# PCB.net
KiCad netlist of a schematic drawn in EAGLE
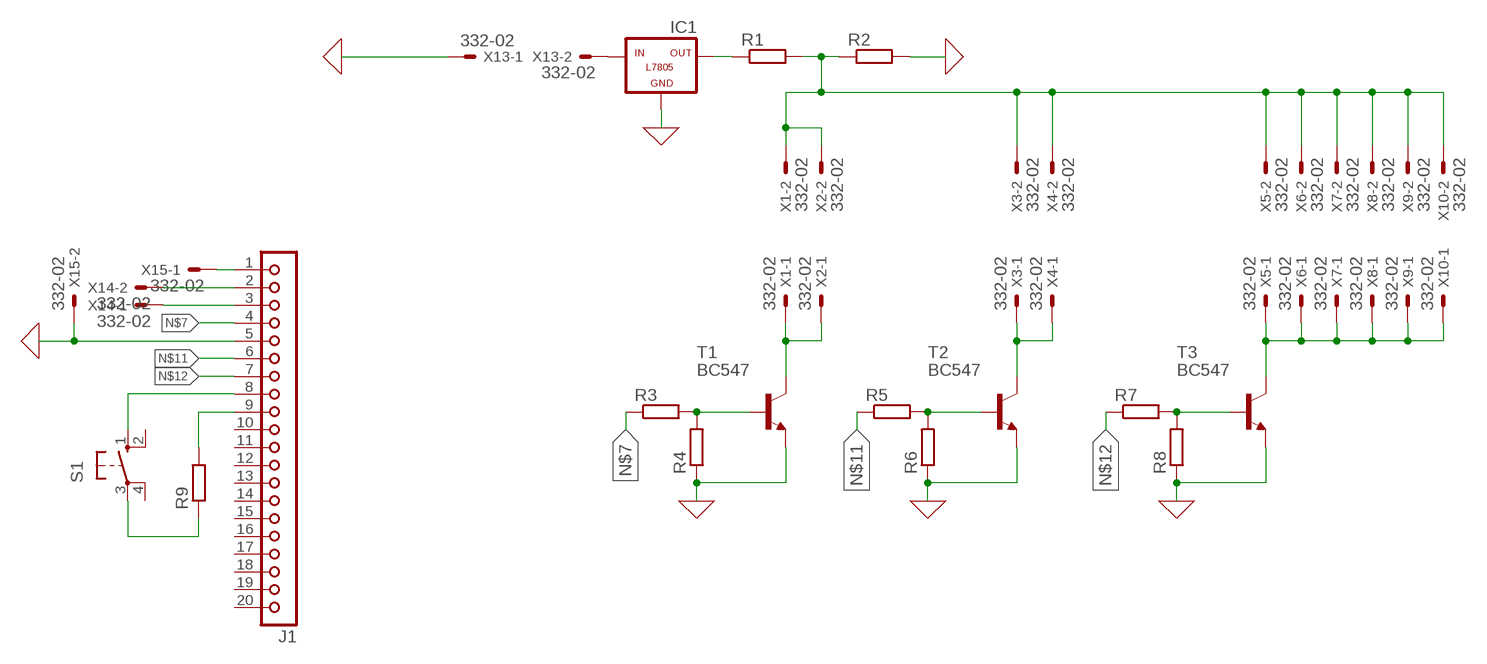
[diagram p0: schematic, sheet 1]

(export (version "E")
  (design (tool "Eeschema 10.0.6"))
  (components
    (comp (ref "IC1")
      (value "L7805")
      (footprint "eagle-import:78XXL")
      (libsource (lib "eagle-import") (part "L7805"))
    )
    (comp (ref "J1")
      (value "JBK20L")
      (footprint "eagle-import:JBK20L")
      (libsource (lib "eagle-import") (part "JBK20L"))
    )
    (comp (ref "R1")
      (value "R-EU_0309/12")
      (footprint "eagle-import:0309_12")
      (libsource (lib "eagle-import") (part "R-EU_0309/12"))
    )
    (comp (ref "R2")
      (value "R-EU_0309/12")
      (footprint "eagle-import:0309_12")
      (libsource (lib "eagle-import") (part "R-EU_0309/12"))
    )
    (comp (ref "R3")
      (value "R-EU_0309/12")
      (footprint "eagle-import:0309_12")
      (libsource (lib "eagle-import") (part "R-EU_0309/12"))
    )
    (comp (ref "R4")
      (value "R-EU_0309/12")
      (footprint "eagle-import:0309_12")
      (libsource (lib "eagle-import") (part "R-EU_0309/12"))
    )
    (comp (ref "R5")
      (value "R-EU_0309/12")
      (footprint "eagle-import:0309_12")
      (libsource (lib "eagle-import") (part "R-EU_0309/12"))
    )
    (comp (ref "R6")
      (value "R-EU_0309/12")
      (footprint "eagle-import:0309_12")
      (libsource (lib "eagle-import") (part "R-EU_0309/12"))
    )
    (comp (ref "R7")
      (value "R-EU_0309/12")
      (footprint "eagle-import:0309_12")
      (libsource (lib "eagle-import") (part "R-EU_0309/12"))
    )
    (comp (ref "R8")
      (value "R-EU_0309/12")
      (footprint "eagle-import:0309_12")
      (libsource (lib "eagle-import") (part "R-EU_0309/12"))
    )
    (comp (ref "R9")
      (value "R-EU_0309/12")
      (footprint "eagle-import:0309_12")
      (libsource (lib "eagle-import") (part "R-EU_0309/12"))
    )
    (comp (ref "S1")
      (value "10-XX")
      (footprint "eagle-import:B3F-10XX")
      (fields (field (name "MPN") "B3F-1000"))
      (libsource (lib "eagle-import") (part "10-XX"))
    )
    (comp (ref "T1")
      (value "BC547")
      (footprint "eagle-import:TO92")
      (libsource (lib "eagle-import") (part "BC547"))
    )
    (comp (ref "T2")
      (value "BC547")
      (footprint "eagle-import:TO92")
      (libsource (lib "eagle-import") (part "BC547"))
    )
    (comp (ref "T3")
      (value "BC547")
      (footprint "eagle-import:TO92")
      (libsource (lib "eagle-import") (part "BC547"))
    )
    (comp (ref "X1")
      (value "332-02")
      (footprint "eagle-import:332-02")
      (libsource (lib "eagle-import") (part "332-02"))
    )
    (comp (ref "X2")
      (value "332-02")
      (footprint "eagle-import:332-02")
      (libsource (lib "eagle-import") (part "332-02"))
    )
    (comp (ref "X3")
      (value "332-02")
      (footprint "eagle-import:332-02")
      (libsource (lib "eagle-import") (part "332-02"))
    )
    (comp (ref "X4")
      (value "332-02")
      (footprint "eagle-import:332-02")
      (libsource (lib "eagle-import") (part "332-02"))
    )
    (comp (ref "X5")
      (value "332-02")
      (footprint "eagle-import:332-02")
      (libsource (lib "eagle-import") (part "332-02"))
    )
    (comp (ref "X6")
      (value "332-02")
      (footprint "eagle-import:332-02")
      (libsource (lib "eagle-import") (part "332-02"))
    )
    (comp (ref "X7")
      (value "332-02")
      (footprint "eagle-import:332-02")
      (libsource (lib "eagle-import") (part "332-02"))
    )
    (comp (ref "X8")
      (value "332-02")
      (footprint "eagle-import:332-02")
      (libsource (lib "eagle-import") (part "332-02"))
    )
    (comp (ref "X9")
      (value "332-02")
      (footprint "eagle-import:332-02")
      (libsource (lib "eagle-import") (part "332-02"))
    )
    (comp (ref "X10")
      (value "332-02")
      (footprint "eagle-import:332-02")
      (libsource (lib "eagle-import") (part "332-02"))
    )
    (comp (ref "X13")
      (value "332-02")
      (footprint "eagle-import:332-02")
      (libsource (lib "eagle-import") (part "332-02"))
    )
    (comp (ref "X14")
      (value "332-02")
      (footprint "eagle-import:332-02")
      (libsource (lib "eagle-import") (part "332-02"))
    )
    (comp (ref "X15")
      (value "332-02")
      (footprint "eagle-import:332-02")
      (libsource (lib "eagle-import") (part "332-02"))
    )
  )
  (nets
    (net (code "1") (name "GND") (class "Default")
      (node (ref "IC1") (pin "GND") (pinfunction "GND_GND") (pintype "input"))
      (node (ref "J1") (pin "5") (pinfunction "5_5") (pintype "passive"))
      (node (ref "R2") (pin "2") (pinfunction "2_2") (pintype "passive"))
      (node (ref "R4") (pin "1") (pinfunction "1_1") (pintype "passive"))
      (node (ref "R6") (pin "1") (pinfunction "1_1") (pintype "passive"))
      (node (ref "R8") (pin "1") (pinfunction "1_1") (pintype "passive"))
      (node (ref "T1") (pin "1") (pinfunction "E_1") (pintype "passive"))
      (node (ref "T2") (pin "1") (pinfunction "E_1") (pintype "passive"))
      (node (ref "T3") (pin "1") (pinfunction "E_1") (pintype "passive"))
      (node (ref "X13") (pin "1") (pinfunction "S_1") (pintype "passive"))
      (node (ref "X15") (pin "2") (pinfunction "S_2") (pintype "passive"))
    )
    (net (code "2") (name "N$7") (class "Default")
      (node (ref "J1") (pin "4") (pinfunction "4_4") (pintype "passive"))
      (node (ref "R3") (pin "1") (pinfunction "1_1") (pintype "passive"))
    )
    (net (code "3") (name "N$11") (class "Default")
      (node (ref "J1") (pin "6") (pinfunction "6_6") (pintype "passive"))
      (node (ref "R5") (pin "1") (pinfunction "1_1") (pintype "passive"))
    )
    (net (code "4") (name "N$12") (class "Default")
      (node (ref "J1") (pin "7") (pinfunction "7_7") (pintype "passive"))
      (node (ref "R7") (pin "1") (pinfunction "1_1") (pintype "passive"))
    )
    (net (code "5") (name "Net-(IC1-PadOUT)") (class "Default")
      (node (ref "IC1") (pin "OUT") (pinfunction "OUT_OUT") (pintype "passive"))
      (node (ref "R1") (pin "1") (pinfunction "1_1") (pintype "passive"))
    )
    (net (code "6") (name "Net-(J1-Pad9)") (class "Default")
      (node (ref "J1") (pin "9") (pinfunction "9_9") (pintype "passive"))
      (node (ref "R9") (pin "2") (pinfunction "2_2") (pintype "passive"))
    )
    (net (code "7") (name "Net-(S1-P)") (class "Default")
      (node (ref "R9") (pin "1") (pinfunction "1_1") (pintype "passive"))
      (node (ref "S1") (pin "3") (pinfunction "P_3") (pintype "passive"))
    )
    (net (code "8") (name "Net-(S1-S)") (class "Default")
      (node (ref "J1") (pin "8") (pinfunction "8_8") (pintype "passive"))
      (node (ref "S1") (pin "1") (pinfunction "S_1") (pintype "passive"))
    )
    (net (code "9") (name "Net-(T1-B)") (class "Default")
      (node (ref "R3") (pin "2") (pinfunction "2_2") (pintype "passive"))
      (node (ref "R4") (pin "2") (pinfunction "2_2") (pintype "passive"))
      (node (ref "T1") (pin "2") (pinfunction "B_2") (pintype "passive"))
    )
    (net (code "10") (name "Net-(T1-C)") (class "Default")
      (node (ref "T1") (pin "3") (pinfunction "C_3") (pintype "passive"))
      (node (ref "X1") (pin "1") (pinfunction "S_1") (pintype "passive"))
      (node (ref "X2") (pin "1") (pinfunction "S_1") (pintype "passive"))
    )
    (net (code "11") (name "Net-(T2-B)") (class "Default")
      (node (ref "R5") (pin "2") (pinfunction "2_2") (pintype "passive"))
      (node (ref "R6") (pin "2") (pinfunction "2_2") (pintype "passive"))
      (node (ref "T2") (pin "2") (pinfunction "B_2") (pintype "passive"))
    )
    (net (code "12") (name "Net-(T2-C)") (class "Default")
      (node (ref "T2") (pin "3") (pinfunction "C_3") (pintype "passive"))
      (node (ref "X3") (pin "1") (pinfunction "S_1") (pintype "passive"))
      (node (ref "X4") (pin "1") (pinfunction "S_1") (pintype "passive"))
    )
    (net (code "13") (name "Net-(T3-B)") (class "Default")
      (node (ref "R7") (pin "2") (pinfunction "2_2") (pintype "passive"))
      (node (ref "R8") (pin "2") (pinfunction "2_2") (pintype "passive"))
      (node (ref "T3") (pin "2") (pinfunction "B_2") (pintype "passive"))
    )
    (net (code "14") (name "Net-(T3-C)") (class "Default")
      (node (ref "T3") (pin "3") (pinfunction "C_3") (pintype "passive"))
      (node (ref "X10") (pin "1") (pinfunction "S_1") (pintype "passive"))
      (node (ref "X5") (pin "1") (pinfunction "S_1") (pintype "passive"))
      (node (ref "X6") (pin "1") (pinfunction "S_1") (pintype "passive"))
      (node (ref "X7") (pin "1") (pinfunction "S_1") (pintype "passive"))
      (node (ref "X8") (pin "1") (pinfunction "S_1") (pintype "passive"))
      (node (ref "X9") (pin "1") (pinfunction "S_1") (pintype "passive"))
    )
    (net (code "15") (name "Net-(X10B-S)") (class "Default")
      (node (ref "R1") (pin "2") (pinfunction "2_2") (pintype "passive"))
      (node (ref "R2") (pin "1") (pinfunction "1_1") (pintype "passive"))
      (node (ref "X1") (pin "2") (pinfunction "S_2") (pintype "passive"))
      (node (ref "X10") (pin "2") (pinfunction "S_2") (pintype "passive"))
      (node (ref "X2") (pin "2") (pinfunction "S_2") (pintype "passive"))
      (node (ref "X3") (pin "2") (pinfunction "S_2") (pintype "passive"))
      (node (ref "X4") (pin "2") (pinfunction "S_2") (pintype "passive"))
      (node (ref "X5") (pin "2") (pinfunction "S_2") (pintype "passive"))
      (node (ref "X6") (pin "2") (pinfunction "S_2") (pintype "passive"))
      (node (ref "X7") (pin "2") (pinfunction "S_2") (pintype "passive"))
      (node (ref "X8") (pin "2") (pinfunction "S_2") (pintype "passive"))
      (node (ref "X9") (pin "2") (pinfunction "S_2") (pintype "passive"))
    )
    (net (code "16") (name "Net-(X13B-S)") (class "Default")
      (node (ref "IC1") (pin "IN") (pinfunction "IN_IN") (pintype "input"))
      (node (ref "X13") (pin "2") (pinfunction "S_2") (pintype "passive"))
    )
    (net (code "17") (name "Net-(X14A-S)") (class "Default")
      (node (ref "J1") (pin "3") (pinfunction "3_3") (pintype "passive"))
      (node (ref "X14") (pin "1") (pinfunction "S_1") (pintype "passive"))
    )
    (net (code "18") (name "Net-(X14B-S)") (class "Default")
      (node (ref "J1") (pin "2") (pinfunction "2_2") (pintype "passive"))
      (node (ref "X14") (pin "2") (pinfunction "S_2") (pintype "passive"))
    )
    (net (code "19") (name "Net-(X15A-S)") (class "Default")
      (node (ref "J1") (pin "1") (pinfunction "1_1") (pintype "passive"))
      (node (ref "X15") (pin "1") (pinfunction "S_1") (pintype "passive"))
    )
    (net (code "20") (name "unconnected-(J1-Pad10)") (class "Default")
      (node (ref "J1") (pin "10") (pinfunction "10_10") (pintype "passive"))
    )
    (net (code "21") (name "unconnected-(J1-Pad11)") (class "Default")
      (node (ref "J1") (pin "11") (pinfunction "11_11") (pintype "passive"))
    )
    (net (code "22") (name "unconnected-(J1-Pad12)") (class "Default")
      (node (ref "J1") (pin "12") (pinfunction "12_12") (pintype "passive"))
    )
    (net (code "23") (name "unconnected-(J1-Pad13)") (class "Default")
      (node (ref "J1") (pin "13") (pinfunction "13_13") (pintype "passive"))
    )
    (net (code "24") (name "unconnected-(J1-Pad14)") (class "Default")
      (node (ref "J1") (pin "14") (pinfunction "14_14") (pintype "passive"))
    )
    (net (code "25") (name "unconnected-(J1-Pad15)") (class "Default")
      (node (ref "J1") (pin "15") (pinfunction "15_15") (pintype "passive"))
    )
    (net (code "26") (name "unconnected-(J1-Pad16)") (class "Default")
      (node (ref "J1") (pin "16") (pinfunction "16_16") (pintype "passive"))
    )
    (net (code "27") (name "unconnected-(J1-Pad17)") (class "Default")
      (node (ref "J1") (pin "17") (pinfunction "17_17") (pintype "passive"))
    )
    (net (code "28") (name "unconnected-(J1-Pad18)") (class "Default")
      (node (ref "J1") (pin "18") (pinfunction "18_18") (pintype "passive"))
    )
    (net (code "29") (name "unconnected-(J1-Pad19)") (class "Default")
      (node (ref "J1") (pin "19") (pinfunction "19_19") (pintype "passive"))
    )
    (net (code "30") (name "unconnected-(J1-Pad20)") (class "Default")
      (node (ref "J1") (pin "20") (pinfunction "20_20") (pintype "passive"))
    )
    (net (code "31") (name "unconnected-(S1-P1-Pad4)") (class "Default")
      (node (ref "S1") (pin "4") (pinfunction "P1_4") (pintype "passive"))
    )
    (net (code "32") (name "unconnected-(S1-S1-Pad2)") (class "Default")
      (node (ref "S1") (pin "2") (pinfunction "S1_2") (pintype "passive"))
    )
  )
)
